# design.net
KiCad netlist of a schematic drawn in Altium Designer
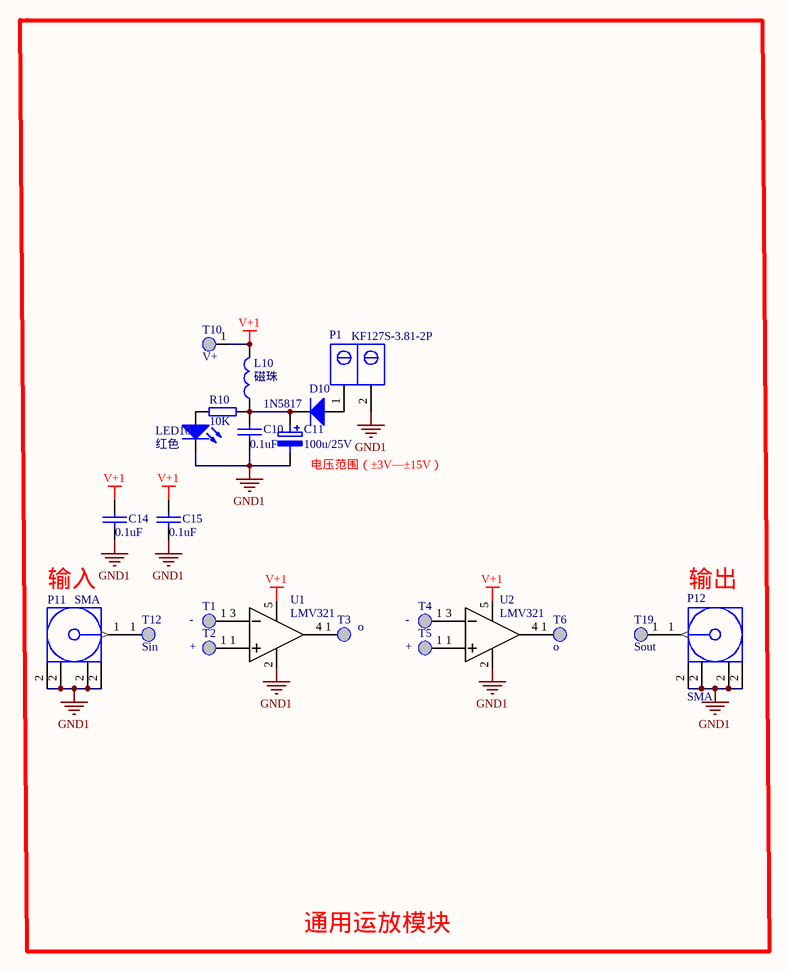
[diagram p0: 运放单元.schdoc]

(export (version "E")
  (design (tool "Eeschema 10.0.6"))
  (components
    (comp (ref "C10")
      (value "0.1uF")
      (footprint "0805")
      (libsource (lib "Sch_Device_veryaz") (part "电容 贴片 0805"))
    )
    (comp (ref "C11")
      (value "100u/25V")
      (footprint "1206")
      (libsource (lib "Sch_Device_veryaz") (part "电容 贴片 铝电解100u/25V"))
    )
    (comp (ref "C14")
      (value "0.1uF")
      (footprint "0805")
      (libsource (lib "Sch_Device_veryaz") (part "电容 贴片 0805"))
    )
    (comp (ref "C15")
      (value "0.1uF")
      (footprint "0805")
      (libsource (lib "Sch_Device_veryaz") (part "电容 贴片 0805"))
    )
    (comp (ref "D10")
      (value "1N5817")
      (footprint "二极管 贴片 2010")
      (libsource (lib "Sch_Device_veryaz") (part "二极管 贴片1N5817"))
    )
    (comp (ref "L10") (value "磁珠") (footprint "0805") (libsource (lib "Sch_Device_veryaz") (part "磁珠")))
    (comp (ref "LED10")
      (value "红色")
      (footprint "LED0805")
      (libsource (lib "Sch_Device_veryaz") (part "二极管 贴片发光 0805"))
    )
    (comp (ref "P1")
      (value "KF127S-3.81-2P")
      (footprint "KF128-3.81-2P")
      (libsource (lib "Sch_Device_veryaz") (part "连接件 KF127S-3.81-2P"))
    )
    (comp (ref "P11")
      (value "SMA")
      (footprint "天线座 50ohm 侧卧")
      (libsource (lib "Sch_Device_veryaz") (part "联结件 天线座 SMA"))
    )
    (comp (ref "P12")
      (value "SMA")
      (footprint "天线座 50ohm 侧卧")
      (libsource (lib "Sch_Device_veryaz") (part "联结件 天线座 SMA"))
    )
    (comp (ref "R10")
      (value "10K")
      (footprint "0805")
      (libsource (lib "Sch_Device_veryaz") (part "电阻 贴片 0805"))
    )
    (comp (ref "T1") (value "-") (footprint "测试点（圆形）") (libsource (lib "Sch_Device_veryaz") (part "测试点_小")))
    (comp (ref "T2") (value "+") (footprint "测试点（圆形）") (libsource (lib "Sch_Device_veryaz") (part "测试点_小")))
    (comp (ref "T3") (value "o") (footprint "测试点（圆形）") (libsource (lib "") (part "测试点_小_1")))
    (comp (ref "T4") (value "-") (footprint "测试点（圆形）") (libsource (lib "Sch_Device_veryaz") (part "测试点_小")))
    (comp (ref "T5") (value "+") (footprint "测试点（圆形）") (libsource (lib "Sch_Device_veryaz") (part "测试点_小")))
    (comp (ref "T6") (value "o") (footprint "测试点（圆形）") (libsource (lib "") (part "测试点_小_1")))
    (comp (ref "T10") (value "V+") (footprint "测试点（圆形）") (libsource (lib "Sch_Device_veryaz") (part "测试点_小")))
    (comp (ref "T12") (value "Sin") (footprint "测试点（圆形）") (libsource (lib "") (part "测试点_小_1")))
    (comp (ref "T19")
      (value "Sout")
      (footprint "测试点（圆形）")
      (libsource (lib "Sch_Device_veryaz") (part "测试点_小"))
    )
    (comp (ref "U1")
      (value "LMV321")
      (footprint "SOT23-5")
      (libsource (lib "Sch_Device_veryaz") (part "贴片芯片 LMV321"))
    )
    (comp (ref "U2")
      (value "LMV321")
      (footprint "SOT23-5")
      (libsource (lib "Sch_Device_veryaz") (part "贴片芯片 LMV321"))
    )
  )
  (nets
    (net (code "1") (name "GND1") (class "Default")
      (node (ref "C10") (pin "1") (pintype "passive"))
      (node (ref "C11") (pin "2") (pintype "passive"))
      (node (ref "C14") (pin "1") (pintype "passive"))
      (node (ref "C15") (pin "1") (pintype "passive"))
      (node (ref "LED10") (pin "2") (pinfunction "K_2") (pintype "passive"))
      (node (ref "P1") (pin "2") (pinfunction "2_2") (pintype "passive"))
      (node (ref "P11") (pin "2") (pinfunction "2_2") (pintype "power_in"))
      (node (ref "P12") (pin "2") (pinfunction "2_2") (pintype "power_in"))
      (node (ref "U1") (pin "2") (pinfunction "GND_2") (pintype "passive"))
      (node (ref "U2") (pin "2") (pinfunction "GND_2") (pintype "passive"))
    )
    (net (code "2") (name "Net-(D10-A)") (class "Default")
      (node (ref "D10") (pin "1") (pinfunction "A_1") (pintype "passive"))
      (node (ref "P1") (pin "1") (pinfunction "1_1") (pintype "passive"))
    )
    (net (code "3") (name "Net-(D10-K)") (class "Default")
      (node (ref "C10") (pin "2") (pintype "passive"))
      (node (ref "C11") (pin "1") (pintype "passive"))
      (node (ref "D10") (pin "2") (pinfunction "K_2") (pintype "passive"))
      (node (ref "L10") (pin "1") (pinfunction "1_1") (pintype "passive"))
      (node (ref "R10") (pin "2") (pinfunction "2_2") (pintype "passive"))
    )
    (net (code "4") (name "Net-(LED10-A)") (class "Default")
      (node (ref "LED10") (pin "1") (pinfunction "A_1") (pintype "passive"))
      (node (ref "R10") (pin "1") (pinfunction "1_1") (pintype "passive"))
    )
    (net (code "5") (name "Net-(P11-Signal)") (class "Default")
      (node (ref "P11") (pin "1") (pinfunction "Signal_1") (pintype "output"))
      (node (ref "T12") (pin "1") (pinfunction "1_1") (pintype "passive"))
    )
    (net (code "6") (name "Net-(P12-Signal)") (class "Default")
      (node (ref "P12") (pin "1") (pinfunction "Signal_1") (pintype "output"))
      (node (ref "T19") (pin "1") (pinfunction "1_1") (pintype "passive"))
    )
    (net (code "7") (name "Net-(U1-IN+)") (class "Default")
      (node (ref "T2") (pin "1") (pinfunction "1_1") (pintype "passive"))
      (node (ref "U1") (pin "1") (pinfunction "IN+_1") (pintype "passive"))
    )
    (net (code "8") (name "Net-(U1-IN-)") (class "Default")
      (node (ref "T1") (pin "1") (pinfunction "1_1") (pintype "passive"))
      (node (ref "U1") (pin "3") (pinfunction "IN-_3") (pintype "passive"))
    )
    (net (code "9") (name "Net-(U1-OUT)") (class "Default")
      (node (ref "T3") (pin "1") (pinfunction "1_1") (pintype "passive"))
      (node (ref "U1") (pin "4") (pinfunction "OUT_4") (pintype "passive"))
    )
    (net (code "10") (name "Net-(U2-IN+)") (class "Default")
      (node (ref "T5") (pin "1") (pinfunction "1_1") (pintype "passive"))
      (node (ref "U2") (pin "1") (pinfunction "IN+_1") (pintype "passive"))
    )
    (net (code "11") (name "Net-(U2-IN-)") (class "Default")
      (node (ref "T4") (pin "1") (pinfunction "1_1") (pintype "passive"))
      (node (ref "U2") (pin "3") (pinfunction "IN-_3") (pintype "passive"))
    )
    (net (code "12") (name "Net-(U2-OUT)") (class "Default")
      (node (ref "T6") (pin "1") (pinfunction "1_1") (pintype "passive"))
      (node (ref "U2") (pin "4") (pinfunction "OUT_4") (pintype "passive"))
    )
    (net (code "13") (name "V+1") (class "Default")
      (node (ref "C14") (pin "2") (pintype "passive"))
      (node (ref "C15") (pin "2") (pintype "passive"))
      (node (ref "L10") (pin "2") (pinfunction "2_2") (pintype "passive"))
      (node (ref "T10") (pin "1") (pinfunction "1_1") (pintype "passive"))
      (node (ref "U1") (pin "5") (pinfunction "VCC_5") (pintype "passive"))
      (node (ref "U2") (pin "5") (pinfunction "VCC_5") (pintype "passive"))
    )
  )
)
